# SCH_Focus_Dial.net
KiCad netlist of a schematic drawn in EasyEDA
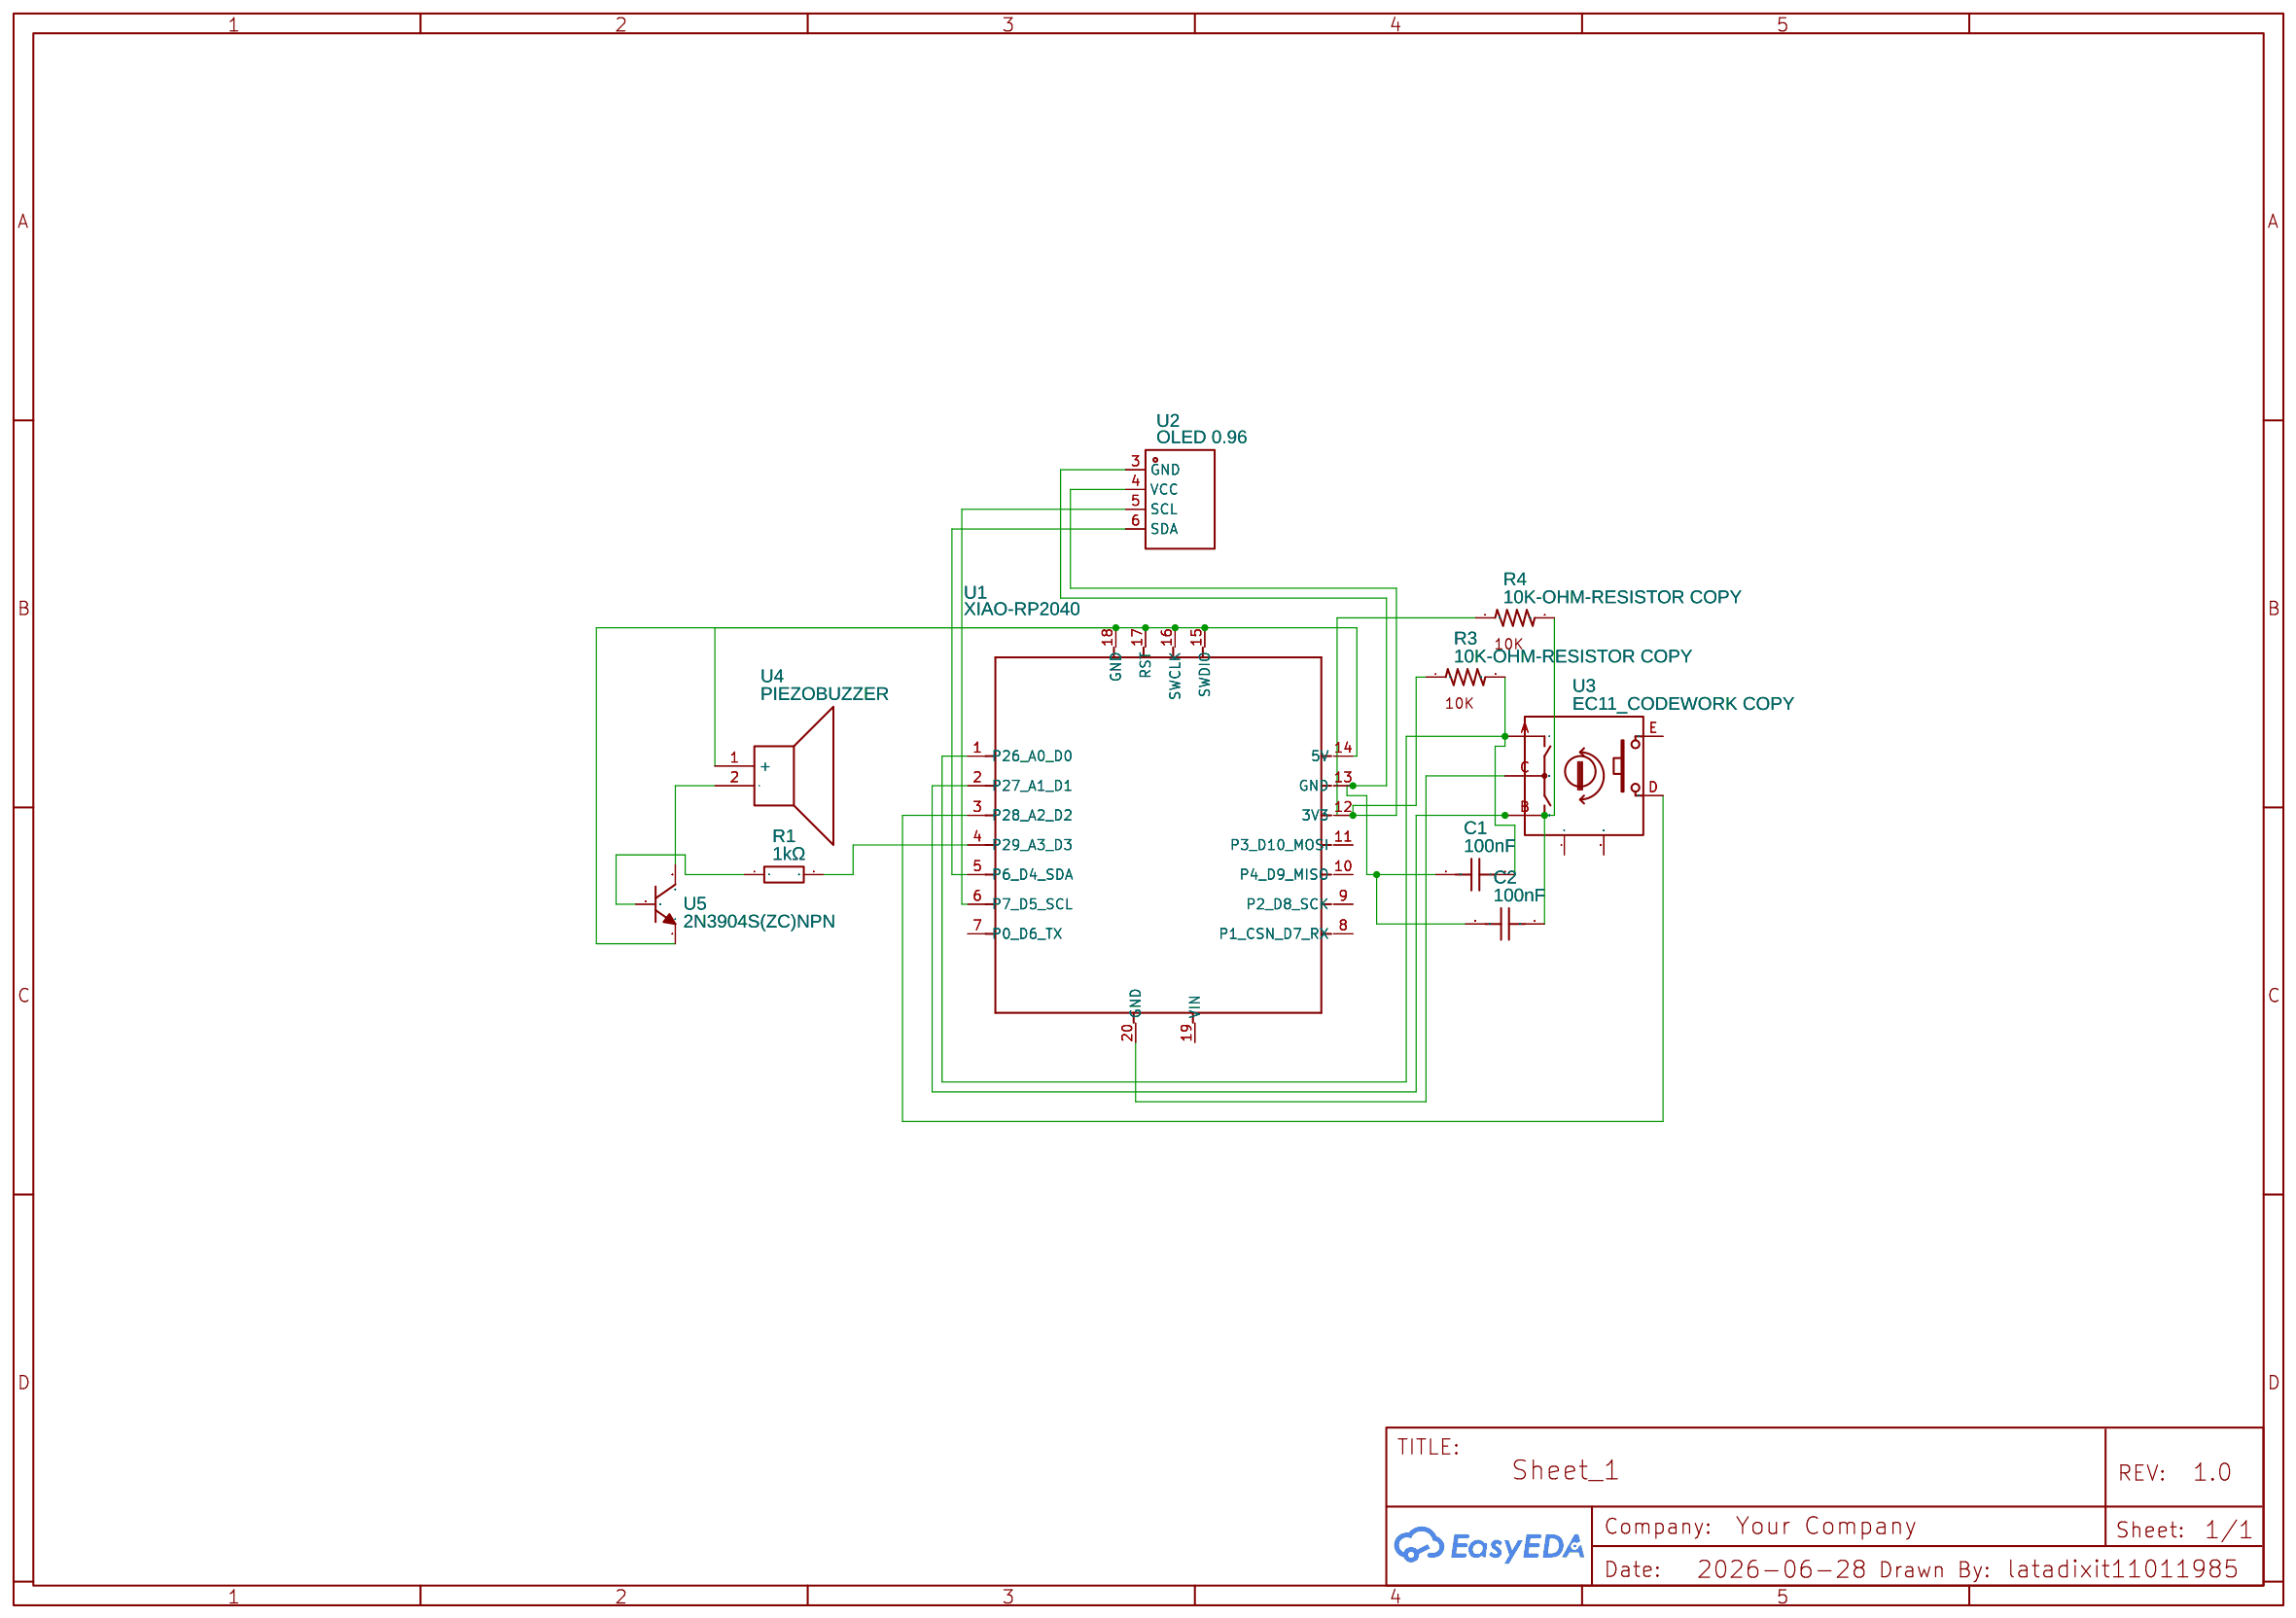
[diagram p0: schematic sheet]

(export (version "E")
  (design (tool "Eeschema 10.0.6"))
  (components
    (comp (ref "C1") (value "100nF") (libsource (lib "") (part "C_0603_US")))
    (comp (ref "C2") (value "100nF") (libsource (lib "") (part "C_0603_US")))
    (comp (ref "R1")
      (value "1kΩ")
      (fields (field (name "Manufacturer Part") "RC0402FR-071KL") (field (name "Manufacturer") "YAGEO(国巨)"))
      (libsource (lib "") (part "1K-OHM-RESISTOR"))
    )
    (comp (ref "R3") (value "10K-OHM-RESISTOR COPY") (libsource (lib "") (part "10K-OHM-RESISTOR")))
    (comp (ref "R4") (value "10K-OHM-RESISTOR COPY") (libsource (lib "") (part "10K-OHM-RESISTOR")))
    (comp (ref "U1") (value "XIAO-RP2040") (libsource (lib "") (part "XIAO-RP2040")))
    (comp (ref "U2")
      (value "OLED 0.96")
      (fields
        (field (name "Manufacturer Part") "ZJY096S0700BG01蓝色")
        (field (name "Manufacturer") "AZDelivery")
      )
      (libsource (lib "") (part "OLED 0.96 COPY"))
    )
    (comp (ref "U3")
      (value "EC11_CODEWORK COPY")
      (fields (field (name "Manufacturer Part") "EC110201E2J-HA1-005"))
      (libsource (lib "") (part "EC11_CODEWORK COPY"))
    )
    (comp (ref "U4") (value "PIEZOBUZZER") (libsource (lib "") (part "PIEZOBUZZER")))
    (comp (ref "U5") (value "2N3904S(ZC)NPN") (libsource (lib "") (part "2N3904S(ZC)NPN")))
  )
  (nets
    (net (code "1") (name "Net-(U1-3V3)") (class "Default")
      (node (ref "R3") (pin "1") (pinfunction "1_1") (pintype "unspecified"))
      (node (ref "R4") (pin "1") (pinfunction "1_1") (pintype "unspecified"))
      (node (ref "U1") (pin "12") (pinfunction "3V3_12") (pintype "bidirectional"))
      (node (ref "U2") (pin "4") (pinfunction "VCC_4") (pintype "unspecified"))
    )
    (net (code "2") (name "Net-(U1-5V)") (class "Default")
      (node (ref "U1") (pin "14") (pinfunction "5V_14") (pintype "bidirectional"))
      (node (ref "U1") (pin "15") (pinfunction "SWDIO_15") (pintype "bidirectional"))
      (node (ref "U1") (pin "16") (pinfunction "SWCLK_16") (pintype "bidirectional"))
      (node (ref "U1") (pin "17") (pinfunction "RST_17") (pintype "bidirectional"))
      (node (ref "U1") (pin "18") (pinfunction "GND_18") (pintype "bidirectional"))
      (node (ref "U4") (pin "1") (pinfunction "+_1") (pintype "unspecified"))
      (node (ref "U5") (pin "2") (pinfunction "E_2") (pintype "input"))
    )
    (net (code "3") (name "Net-(U1-GND-Pad20)") (class "Default")
      (node (ref "U1") (pin "20") (pinfunction "GND_20") (pintype "bidirectional"))
      (node (ref "U3") (pin "C") (pinfunction "C_C") (pintype "unspecified"))
    )
    (net (code "4") (name "Net-(U1-P6_D4_SDA)") (class "Default")
      (node (ref "U1") (pin "5") (pinfunction "P6_D4_SDA_5") (pintype "bidirectional"))
      (node (ref "U2") (pin "6") (pinfunction "SDA_6") (pintype "unspecified"))
    )
    (net (code "5") (name "Net-(U1-P7_D5_SCL)") (class "Default")
      (node (ref "U1") (pin "6") (pinfunction "P7_D5_SCL_6") (pintype "bidirectional"))
      (node (ref "U2") (pin "5") (pinfunction "SCL_5") (pintype "unspecified"))
    )
    (net (code "6") (name "Net-(U1-P26_A0_D0)") (class "Default")
      (node (ref "C1") (pin "1") (pinfunction "1_1") (pintype "unspecified"))
      (node (ref "R3") (pin "2") (pinfunction "2_2") (pintype "unspecified"))
      (node (ref "U1") (pin "1") (pinfunction "P26_A0_D0_1") (pintype "bidirectional"))
      (node (ref "U3") (pin "A") (pinfunction "A_A") (pintype "unspecified"))
    )
    (net (code "7") (name "Net-(U1-P27_A1_D1)") (class "Default")
      (node (ref "C2") (pin "1") (pinfunction "1_1") (pintype "unspecified"))
      (node (ref "R4") (pin "2") (pinfunction "2_2") (pintype "unspecified"))
      (node (ref "U1") (pin "2") (pinfunction "P27_A1_D1_2") (pintype "bidirectional"))
      (node (ref "U3") (pin "B") (pinfunction "B_B") (pintype "unspecified"))
    )
    (net (code "8") (name "Net-(U1-P28_A2_D2)") (class "Default")
      (node (ref "U1") (pin "3") (pinfunction "P28_A2_D2_3") (pintype "bidirectional"))
      (node (ref "U3") (pin "D") (pinfunction "D_D") (pintype "unspecified"))
    )
    (net (code "9") (name "Net-(U1-P29_A3_D3)") (class "Default")
      (node (ref "R1") (pin "2") (pinfunction "2_2") (pintype "input"))
      (node (ref "U1") (pin "4") (pinfunction "P29_A3_D3_4") (pintype "bidirectional"))
    )
    (net (code "10") (name "Net-(U2-GND)") (class "Default")
      (node (ref "C1") (pin "2") (pinfunction "2_2") (pintype "unspecified"))
      (node (ref "C2") (pin "2") (pinfunction "2_2") (pintype "unspecified"))
      (node (ref "U1") (pin "13") (pinfunction "GND_13") (pintype "bidirectional"))
      (node (ref "U2") (pin "3") (pinfunction "GND_3") (pintype "unspecified"))
    )
    (net (code "11") (name "Net-(U4--)") (class "Default")
      (node (ref "U4") (pin "2") (pinfunction "-_2") (pintype "unspecified"))
      (node (ref "U5") (pin "3") (pinfunction "C_3") (pintype "input"))
    )
    (net (code "12") (name "Net-(U5-B)") (class "Default")
      (node (ref "R1") (pin "1") (pinfunction "1_1") (pintype "input"))
      (node (ref "U5") (pin "1") (pinfunction "B_1") (pintype "input"))
    )
    (net (code "13") (name "unconnected-(U1-P0_D6_TX-Pad7)") (class "Default")
      (node (ref "U1") (pin "7") (pinfunction "P0_D6_TX_7") (pintype "bidirectional"))
    )
    (net (code "14") (name "unconnected-(U1-P1_CSN_D7_RX-Pad8)") (class "Default")
      (node (ref "U1") (pin "8") (pinfunction "P1_CSN_D7_RX_8") (pintype "bidirectional"))
    )
    (net (code "15") (name "unconnected-(U1-P2_D8_SCK-Pad9)") (class "Default")
      (node (ref "U1") (pin "9") (pinfunction "P2_D8_SCK_9") (pintype "bidirectional"))
    )
    (net (code "16") (name "unconnected-(U1-P3_D10_MOSI-Pad11)") (class "Default")
      (node (ref "U1") (pin "11") (pinfunction "P3_D10_MOSI_11") (pintype "bidirectional"))
    )
    (net (code "17") (name "unconnected-(U1-P4_D9_MISO-Pad10)") (class "Default")
      (node (ref "U1") (pin "10") (pinfunction "P4_D9_MISO_10") (pintype "bidirectional"))
    )
    (net (code "18") (name "unconnected-(U1-VIN-Pad19)") (class "Default")
      (node (ref "U1") (pin "19") (pinfunction "VIN_19") (pintype "bidirectional"))
    )
    (net (code "19") (name "unconnected-(U3-Pad1)") (class "Default")
      (node (ref "U3") (pin "1") (pinfunction "1_1") (pintype "unspecified"))
    )
    (net (code "20") (name "unconnected-(U3-Pad2)") (class "Default")
      (node (ref "U3") (pin "2") (pinfunction "2_2") (pintype "unspecified"))
    )
    (net (code "21") (name "unconnected-(U3-PadE)") (class "Default")
      (node (ref "U3") (pin "E") (pinfunction "E_E") (pintype "unspecified"))
    )
  )
)
